# RF_Transceiver_LM6002D.net
KiCad netlist of a schematic drawn in Altium Designer
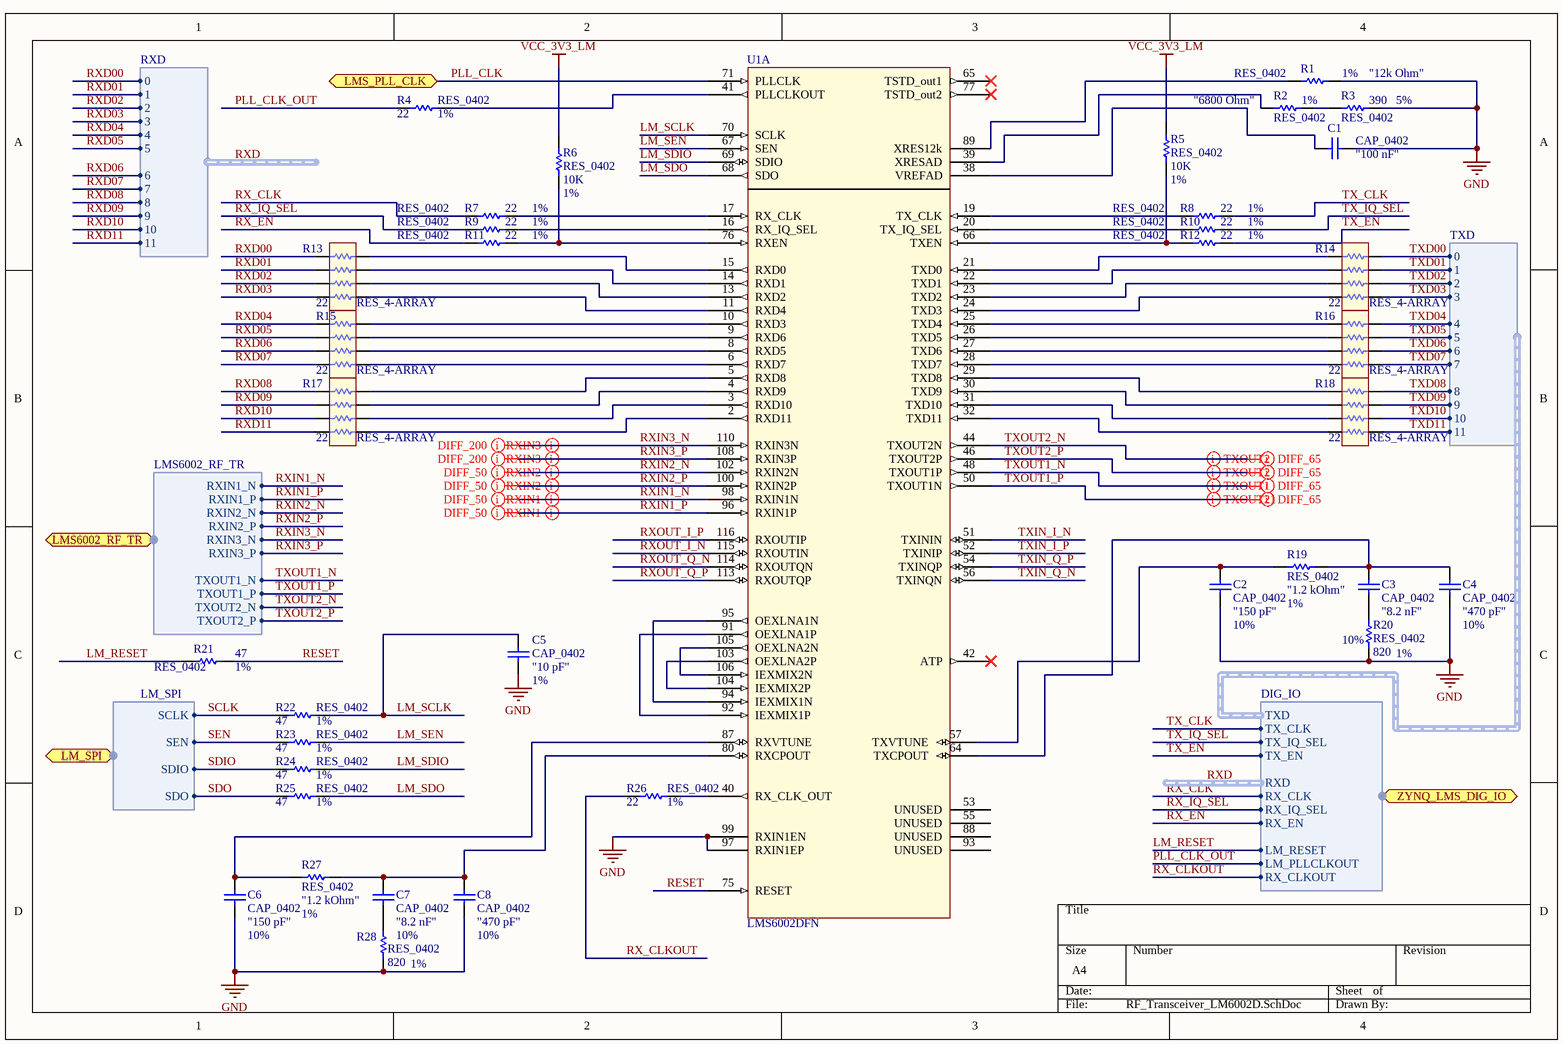
[diagram p0: RF_Transceiver_LM6002D.SchDoc]

(export (version "E")
  (design (tool "Eeschema 10.0.6"))
  (components
    (comp (ref "C1")
      (value "CAP_0402")
      (footprint "CAPC0402(1005)60_N")
      (description "C 100 nF 16 V 0402 X5R")
      (fields
        (field (name "ALTIUM_VALUE") "\"100 nF\"")
        (field (name "PART NUMBER") "\"C0402C104K8PAC\"")
        (field (name "MANUFACTURER") "KEMET")
      )
      (libsource (lib "COMRAD_Database") (part "CAP_0402"))
    )
    (comp (ref "C2")
      (value "CAP_0402")
      (footprint "CAPC0402(1005)60_N")
      (description "C 470pF 50V X7R 10% 0402")
      (fields
        (field (name "ALTIUM_VALUE") "\"150 pF\"")
        (field (name "TOLERANCE") "10%")
        (field (name "PART NUMBER") "\"MCCA000122\"")
        (field (name "MANUFACTURER") "MULTICOMP")
      )
      (libsource (lib "COMRAD_Database") (part "CAP_0402"))
    )
    (comp (ref "C3")
      (value "CAP_0402")
      (footprint "CAPC0402(1005)60_N")
      (description "C 470pF 50V X7R 10% 0402")
      (fields
        (field (name "ALTIUM_VALUE") "\"8.2 nF\"")
        (field (name "TOLERANCE") "10%")
        (field (name "PART NUMBER") "\"MCCA000039\"")
        (field (name "MANUFACTURER") "MULTICOMP")
      )
      (libsource (lib "COMRAD_Database") (part "CAP_0402"))
    )
    (comp (ref "C4")
      (value "CAP_0402")
      (footprint "CAPC0402(1005)60_N")
      (description "C 470pF 50V X7R 10% 0402")
      (fields
        (field (name "ALTIUM_VALUE") "\"470 pF\"")
        (field (name "TOLERANCE") "10%")
        (field (name "PART NUMBER") "\"MCCA000132\"")
        (field (name "MANUFACTURER") "MULTICOMP")
      )
      (libsource (lib "COMRAD_Database") (part "CAP_0402"))
    )
    (comp (ref "C5")
      (value "CAP_0402")
      (footprint "CAPC0402(1005)60_N")
      (description "C 10pF 1% 50V NP0 0402")
      (fields
        (field (name "ALTIUM_VALUE") "\"10 pF\"")
        (field (name "TOLERANCE") "1%")
        (field (name "PART NUMBER") "\"MC0402N100F500CT\"")
        (field (name "MANUFACTURER") "MULTICOMP")
      )
      (libsource (lib "COMRAD_Database") (part "CAP_0402"))
    )
    (comp (ref "C6")
      (value "CAP_0402")
      (footprint "CAPC0402(1005)60_N")
      (description "C 470pF 50V X7R 10% 0402")
      (fields
        (field (name "ALTIUM_VALUE") "\"150 pF\"")
        (field (name "TOLERANCE") "10%")
        (field (name "PART NUMBER") "\"MCCA000122\"")
        (field (name "MANUFACTURER") "MULTICOMP")
      )
      (libsource (lib "COMRAD_Database") (part "CAP_0402"))
    )
    (comp (ref "C7")
      (value "CAP_0402")
      (footprint "CAPC0402(1005)60_N")
      (description "C 470pF 50V X7R 10% 0402")
      (fields
        (field (name "ALTIUM_VALUE") "\"8.2 nF\"")
        (field (name "TOLERANCE") "10%")
        (field (name "PART NUMBER") "\"MCCA000039\"")
        (field (name "MANUFACTURER") "MULTICOMP")
      )
      (libsource (lib "COMRAD_Database") (part "CAP_0402"))
    )
    (comp (ref "C8")
      (value "CAP_0402")
      (footprint "CAPC0402(1005)60_N")
      (description "C 470pF 50V X7R 10% 0402")
      (fields
        (field (name "ALTIUM_VALUE") "\"470 pF\"")
        (field (name "TOLERANCE") "10%")
        (field (name "PART NUMBER") "\"MCCA000132\"")
        (field (name "MANUFACTURER") "MULTICOMP")
      )
      (libsource (lib "COMRAD_Database") (part "CAP_0402"))
    )
    (comp (ref "R1")
      (value "RES_0402")
      (footprint "RESC0402(1005)_N")
      (description "R 12 kOhm 1 % 63 mW 0402")
      (fields
        (field (name "ALTIUM_VALUE") "\"12k Ohm\"")
        (field (name "TOLERANCE") "1%")
        (field (name "PART NUMBER") "\"MC 0.0625W 0402 1% 12K\"")
        (field (name "MANUFACTURER") "MULTICOMP")
      )
      (libsource (lib "COMRAD_Database") (part "RES_0402"))
    )
    (comp (ref "R2")
      (value "RES_0402")
      (footprint "RESC0402(1005)_N")
      (description "R 6800 Ohm 1 % 63 mW 0402")
      (fields
        (field (name "ALTIUM_VALUE") "\"6800 Ohm\"")
        (field (name "TOLERANCE") "1%")
        (field (name "PART NUMBER") "\"232270676802\"")
        (field (name "MANUFACTURER") "PHYCOMP")
      )
      (libsource (lib "COMRAD_Database") (part "RES_0402"))
    )
    (comp (ref "R3")
      (value "RES_0402")
      (footprint "RESC0402(1005)_N")
      (description "390 ohm, 5%, 1/16W, 0402")
      (fields
        (field (name "ALTIUM_VALUE") "390")
        (field (name "TOLERANCE") "5%")
        (field (name "PART NUMBER") "RC0402JR-07390RL")
        (field (name "MANUFACTURER") "Yageo America")
      )
      (libsource (lib "COMRAD_Database") (part "RES_0402"))
    )
    (comp (ref "R4")
      (value "RES_0402")
      (footprint "RESC0402(1005)_N")
      (description "RES 22.0 OHM 1/10W 1% 0402 SMD")
      (fields
        (field (name "ALTIUM_VALUE") "22")
        (field (name "TOLERANCE") "1%")
        (field (name "PART NUMBER") "ERJ-2RKF22R0X")
        (field (name "MANUFACTURER") "Panasonic Electronic Components")
      )
      (libsource (lib "COMRAD_Database") (part "RES_0402"))
    )
    (comp (ref "R5")
      (value "RES_0402")
      (footprint "RESC0402(1005)_N")
      (description "RES 10.0K OHM 1/10W 1% 0402 SMD")
      (fields
        (field (name "ALTIUM_VALUE") "10K")
        (field (name "TOLERANCE") "1%")
        (field (name "PART NUMBER") "ERJ-2RKF1002X")
        (field (name "MANUFACTURER") "Panasonic Electronic Components")
      )
      (libsource (lib "COMRAD_Database") (part "RES_0402"))
    )
    (comp (ref "R6")
      (value "RES_0402")
      (footprint "RESC0402(1005)_N")
      (description "RES 10.0K OHM 1/10W 1% 0402 SMD")
      (fields
        (field (name "ALTIUM_VALUE") "10K")
        (field (name "TOLERANCE") "1%")
        (field (name "PART NUMBER") "ERJ-2RKF1002X")
        (field (name "MANUFACTURER") "Panasonic Electronic Components")
      )
      (libsource (lib "COMRAD_Database") (part "RES_0402"))
    )
    (comp (ref "R7")
      (value "RES_0402")
      (footprint "RESC0402(1005)_N")
      (description "RES 22.0 OHM 1/10W 1% 0402 SMD")
      (fields
        (field (name "ALTIUM_VALUE") "22")
        (field (name "TOLERANCE") "1%")
        (field (name "PART NUMBER") "ERJ-2RKF22R0X")
        (field (name "MANUFACTURER") "Panasonic Electronic Components")
      )
      (libsource (lib "COMRAD_Database") (part "RES_0402"))
    )
    (comp (ref "R8")
      (value "RES_0402")
      (footprint "RESC0402(1005)_N")
      (description "RES 22.0 OHM 1/10W 1% 0402 SMD")
      (fields
        (field (name "ALTIUM_VALUE") "22")
        (field (name "TOLERANCE") "1%")
        (field (name "PART NUMBER") "ERJ-2RKF22R0X")
        (field (name "MANUFACTURER") "Panasonic Electronic Components")
      )
      (libsource (lib "COMRAD_Database") (part "RES_0402"))
    )
    (comp (ref "R9")
      (value "RES_0402")
      (footprint "RESC0402(1005)_N")
      (description "RES 22.0 OHM 1/10W 1% 0402 SMD")
      (fields
        (field (name "ALTIUM_VALUE") "22")
        (field (name "TOLERANCE") "1%")
        (field (name "PART NUMBER") "ERJ-2RKF22R0X")
        (field (name "MANUFACTURER") "Panasonic Electronic Components")
      )
      (libsource (lib "COMRAD_Database") (part "RES_0402"))
    )
    (comp (ref "R10")
      (value "RES_0402")
      (footprint "RESC0402(1005)_N")
      (description "RES 22.0 OHM 1/10W 1% 0402 SMD")
      (fields
        (field (name "ALTIUM_VALUE") "22")
        (field (name "TOLERANCE") "1%")
        (field (name "PART NUMBER") "ERJ-2RKF22R0X")
        (field (name "MANUFACTURER") "Panasonic Electronic Components")
      )
      (libsource (lib "COMRAD_Database") (part "RES_0402"))
    )
    (comp (ref "R11")
      (value "RES_0402")
      (footprint "RESC0402(1005)_N")
      (description "RES 22.0 OHM 1/10W 1% 0402 SMD")
      (fields
        (field (name "ALTIUM_VALUE") "22")
        (field (name "TOLERANCE") "1%")
        (field (name "PART NUMBER") "ERJ-2RKF22R0X")
        (field (name "MANUFACTURER") "Panasonic Electronic Components")
      )
      (libsource (lib "COMRAD_Database") (part "RES_0402"))
    )
    (comp (ref "R12")
      (value "RES_0402")
      (footprint "RESC0402(1005)_N")
      (description "RES 22.0 OHM 1/10W 1% 0402 SMD")
      (fields
        (field (name "ALTIUM_VALUE") "22")
        (field (name "TOLERANCE") "1%")
        (field (name "PART NUMBER") "ERJ-2RKF22R0X")
        (field (name "MANUFACTURER") "Panasonic Electronic Components")
      )
      (libsource (lib "COMRAD_Database") (part "RES_0402"))
    )
    (comp (ref "R13")
      (value "RES_4-ARRAY")
      (footprint "RES_4-ARRAY_YC124-JR-0722RL")
      (description "RES ARRAY 22 OHM 4 RES 0804")
      (fields
        (field (name "ALTIUM_VALUE") "22")
        (field (name "PART NUMBER") "YC124-JR-0722RL")
        (field (name "MANUFACTURER") "Yageo")
      )
      (libsource (lib "COMRAD_Database") (part "RES_4-ARRAY"))
    )
    (comp (ref "R14")
      (value "RES_4-ARRAY")
      (footprint "RES_4-ARRAY_YC124-JR-0722RL")
      (description "RES ARRAY 22 OHM 4 RES 0804")
      (fields
        (field (name "ALTIUM_VALUE") "22")
        (field (name "PART NUMBER") "YC124-JR-0722RL")
        (field (name "MANUFACTURER") "Yageo")
      )
      (libsource (lib "COMRAD_Database") (part "RES_4-ARRAY"))
    )
    (comp (ref "R15")
      (value "RES_4-ARRAY")
      (footprint "RES_4-ARRAY_YC124-JR-0722RL")
      (description "RES ARRAY 22 OHM 4 RES 0804")
      (fields
        (field (name "ALTIUM_VALUE") "22")
        (field (name "PART NUMBER") "YC124-JR-0722RL")
        (field (name "MANUFACTURER") "Yageo")
      )
      (libsource (lib "COMRAD_Database") (part "RES_4-ARRAY"))
    )
    (comp (ref "R16")
      (value "RES_4-ARRAY")
      (footprint "RES_4-ARRAY_YC124-JR-0722RL")
      (description "RES ARRAY 22 OHM 4 RES 0804")
      (fields
        (field (name "ALTIUM_VALUE") "22")
        (field (name "PART NUMBER") "YC124-JR-0722RL")
        (field (name "MANUFACTURER") "Yageo")
      )
      (libsource (lib "COMRAD_Database") (part "RES_4-ARRAY"))
    )
    (comp (ref "R17")
      (value "RES_4-ARRAY")
      (footprint "RES_4-ARRAY_YC124-JR-0722RL")
      (description "RES ARRAY 22 OHM 4 RES 0804")
      (fields
        (field (name "ALTIUM_VALUE") "22")
        (field (name "PART NUMBER") "YC124-JR-0722RL")
        (field (name "MANUFACTURER") "Yageo")
      )
      (libsource (lib "COMRAD_Database") (part "RES_4-ARRAY"))
    )
    (comp (ref "R18")
      (value "RES_4-ARRAY")
      (footprint "RES_4-ARRAY_YC124-JR-0722RL")
      (description "RES ARRAY 22 OHM 4 RES 0804")
      (fields
        (field (name "ALTIUM_VALUE") "22")
        (field (name "PART NUMBER") "YC124-JR-0722RL")
        (field (name "MANUFACTURER") "Yageo")
      )
      (libsource (lib "COMRAD_Database") (part "RES_4-ARRAY"))
    )
    (comp (ref "R19")
      (value "RES_0402")
      (footprint "RESC0402(1005)_N")
      (description "R 1k2 Ohm 1% 63mV 0402")
      (fields
        (field (name "ALTIUM_VALUE") "\"1.2 kOhm\"")
        (field (name "TOLERANCE") "1%")
        (field (name "PART NUMBER") "\"CRCW04021K20FKEAHP\"")
        (field (name "MANUFACTURER") "VISHAY DRALORIC")
      )
      (libsource (lib "COMRAD_Database") (part "RES_0402"))
    )
    (comp (ref "R20")
      (value "RES_0402")
      (footprint "RESC0402(1005)_N")
      (description "RES 820 OHM 1/10W 1% 0402 SMD")
      (fields
        (field (name "ALTIUM_VALUE") "820")
        (field (name "TOLERANCE") "1%")
        (field (name "PART NUMBER") "ERJ-2RKF8200X")
        (field (name "MANUFACTURER") "Panasonic Electronic Components")
      )
      (libsource (lib "COMRAD_Database") (part "RES_0402"))
    )
    (comp (ref "R21")
      (value "RES_0402")
      (footprint "RESC0402(1005)_N")
      (description "RES 47.0 OHM 1/10W 1% 0402 SMD")
      (fields
        (field (name "ALTIUM_VALUE") "47")
        (field (name "TOLERANCE") "1%")
        (field (name "PART NUMBER") "ERJ-2RKF47R0X")
        (field (name "MANUFACTURER") "Panasonic Electronic Components")
      )
      (libsource (lib "COMRAD_Database") (part "RES_0402"))
    )
    (comp (ref "R22")
      (value "RES_0402")
      (footprint "RESC0402(1005)_N")
      (description "RES 47.0 OHM 1/10W 1% 0402 SMD")
      (fields
        (field (name "ALTIUM_VALUE") "47")
        (field (name "TOLERANCE") "1%")
        (field (name "PART NUMBER") "ERJ-2RKF47R0X")
        (field (name "MANUFACTURER") "Panasonic Electronic Components")
      )
      (libsource (lib "COMRAD_Database") (part "RES_0402"))
    )
    (comp (ref "R23")
      (value "RES_0402")
      (footprint "RESC0402(1005)_N")
      (description "RES 47.0 OHM 1/10W 1% 0402 SMD")
      (fields
        (field (name "ALTIUM_VALUE") "47")
        (field (name "TOLERANCE") "1%")
        (field (name "PART NUMBER") "ERJ-2RKF47R0X")
        (field (name "MANUFACTURER") "Panasonic Electronic Components")
      )
      (libsource (lib "COMRAD_Database") (part "RES_0402"))
    )
    (comp (ref "R24")
      (value "RES_0402")
      (footprint "RESC0402(1005)_N")
      (description "RES 47.0 OHM 1/10W 1% 0402 SMD")
      (fields
        (field (name "ALTIUM_VALUE") "47")
        (field (name "TOLERANCE") "1%")
        (field (name "PART NUMBER") "ERJ-2RKF47R0X")
        (field (name "MANUFACTURER") "Panasonic Electronic Components")
      )
      (libsource (lib "COMRAD_Database") (part "RES_0402"))
    )
    (comp (ref "R25")
      (value "RES_0402")
      (footprint "RESC0402(1005)_N")
      (description "RES 47.0 OHM 1/10W 1% 0402 SMD")
      (fields
        (field (name "ALTIUM_VALUE") "47")
        (field (name "TOLERANCE") "1%")
        (field (name "PART NUMBER") "ERJ-2RKF47R0X")
        (field (name "MANUFACTURER") "Panasonic Electronic Components")
      )
      (libsource (lib "COMRAD_Database") (part "RES_0402"))
    )
    (comp (ref "R26")
      (value "RES_0402")
      (footprint "RESC0402(1005)_N")
      (description "RES 22.0 OHM 1/10W 1% 0402 SMD")
      (fields
        (field (name "ALTIUM_VALUE") "22")
        (field (name "TOLERANCE") "1%")
        (field (name "PART NUMBER") "ERJ-2RKF22R0X")
        (field (name "MANUFACTURER") "Panasonic Electronic Components")
      )
      (libsource (lib "COMRAD_Database") (part "RES_0402"))
    )
    (comp (ref "R27")
      (value "RES_0402")
      (footprint "RESC0402(1005)_N")
      (description "R 1k2 Ohm 1% 63mV 0402")
      (fields
        (field (name "ALTIUM_VALUE") "\"1.2 kOhm\"")
        (field (name "TOLERANCE") "1%")
        (field (name "PART NUMBER") "\"CRCW04021K20FKEAHP\"")
        (field (name "MANUFACTURER") "VISHAY DRALORIC")
      )
      (libsource (lib "COMRAD_Database") (part "RES_0402"))
    )
    (comp (ref "R28")
      (value "RES_0402")
      (footprint "RESC0402(1005)_N")
      (description "RES 820 OHM 1/10W 1% 0402 SMD")
      (fields
        (field (name "ALTIUM_VALUE") "820")
        (field (name "TOLERANCE") "1%")
        (field (name "PART NUMBER") "ERJ-2RKF8200X")
        (field (name "MANUFACTURER") "Panasonic Electronic Components")
      )
      (libsource (lib "COMRAD_Database") (part "RES_0402"))
    )
    (comp (ref "U1")
      (value "LMS6002DFN")
      (footprint "RF_Transceiver_LimeMicro_LMS6002D_DQFN-116")
      (description "RF Transceiver LMS6002D, 120 pin DQFN package, 1.8V and 3.3V")
      (fields (field (name "MANUFACTURER") "Lime Micro"))
      (libsource (lib "COMRAD_Database") (part "RF_Transceiver_LimeMicro_LMS6002D"))
    )
  )
  (nets
    (net (code "7") (name "/LM_RESET") (class "Default")
      (node (ref "R21") (pin "1") (pinfunction "1_1") (pintype "passive"))
    )
    (net (code "8") (name "/LM_SCLK") (class "Default")
      (node (ref "C5") (pin "2") (pinfunction "2_2") (pintype "passive"))
      (node (ref "R22") (pin "2") (pinfunction "2_2") (pintype "passive"))
      (node (ref "U1") (pin "70") (pinfunction "SCLK_70") (pintype "input"))
    )
    (net (code "9") (name "/LM_SDIO") (class "Default")
      (node (ref "R24") (pin "2") (pinfunction "2_2") (pintype "passive"))
      (node (ref "U1") (pin "69") (pinfunction "SDIO_69") (pintype "bidirectional"))
    )
    (net (code "10") (name "/LM_SDO") (class "Default")
      (node (ref "R25") (pin "2") (pinfunction "2_2") (pintype "passive"))
      (node (ref "U1") (pin "68") (pinfunction "SDO_68") (pintype "output"))
    )
    (net (code "11") (name "/LM_SEN") (class "Default")
      (node (ref "R23") (pin "2") (pinfunction "2_2") (pintype "passive"))
      (node (ref "U1") (pin "67") (pinfunction "SEN_67") (pintype "input"))
    )
    (net (code "12") (name "/PLL_CLK") (class "Default")
      (node (ref "U1") (pin "71") (pinfunction "PLLCLK_71") (pintype "input"))
    )
    (net (code "13") (name "/PLL_CLK_OUT") (class "Default")
      (node (ref "R4") (pin "1") (pinfunction "1_1") (pintype "passive"))
    )
    (net (code "14") (name "/RESET") (class "Default")
      (node (ref "R21") (pin "2") (pinfunction "2_2") (pintype "passive"))
      (node (ref "U1") (pin "75") (pinfunction "RESET_75") (pintype "input"))
    )
    (net (code "15") (name "/RXD00") (class "Default") (node (ref "R13") (pin "8") (pintype "passive")))
    (net (code "16") (name "/RXD01") (class "Default") (node (ref "R13") (pin "7") (pintype "passive")))
    (net (code "17") (name "/RXD02") (class "Default") (node (ref "R13") (pin "6") (pintype "passive")))
    (net (code "18") (name "/RXD03") (class "Default") (node (ref "R13") (pin "5") (pintype "passive")))
    (net (code "19") (name "/RXD04") (class "Default") (node (ref "R15") (pin "8") (pintype "passive")))
    (net (code "20") (name "/RXD05") (class "Default") (node (ref "R15") (pin "7") (pintype "passive")))
    (net (code "21") (name "/RXD06") (class "Default") (node (ref "R15") (pin "6") (pintype "passive")))
    (net (code "22") (name "/RXD07") (class "Default") (node (ref "R15") (pin "5") (pintype "passive")))
    (net (code "23") (name "/RXD08") (class "Default") (node (ref "R17") (pin "8") (pintype "passive")))
    (net (code "24") (name "/RXD09") (class "Default") (node (ref "R17") (pin "7") (pintype "passive")))
    (net (code "25") (name "/RXD10") (class "Default") (node (ref "R17") (pin "6") (pintype "passive")))
    (net (code "26") (name "/RXD11") (class "Default") (node (ref "R17") (pin "5") (pintype "passive")))
    (net (code "29") (name "/RXIN1_N") (class "Default")
      (node (ref "U1") (pin "98") (pinfunction "RXIN1N_98") (pintype "input"))
    )
    (net (code "30") (name "/RXIN1_P") (class "Default")
      (node (ref "U1") (pin "96") (pinfunction "RXIN1P_96") (pintype "input"))
    )
    (net (code "31") (name "/RXIN2_N") (class "Default")
      (node (ref "U1") (pin "102") (pinfunction "RXIN2N_102") (pintype "input"))
    )
    (net (code "32") (name "/RXIN2_P") (class "Default")
      (node (ref "U1") (pin "100") (pinfunction "RXIN2P_100") (pintype "input"))
    )
    (net (code "33") (name "/RXIN3_N") (class "Default")
      (node (ref "U1") (pin "110") (pinfunction "RXIN3N_110") (pintype "input"))
    )
    (net (code "34") (name "/RXIN3_P") (class "Default")
      (node (ref "U1") (pin "108") (pinfunction "RXIN3P_108") (pintype "input"))
    )
    (net (code "35") (name "/RXOUT_I_N") (class "Default")
      (node (ref "U1") (pin "115") (pinfunction "RXOUTIN_115") (pintype "bidirectional"))
    )
    (net (code "36") (name "/RXOUT_I_P") (class "Default")
      (node (ref "U1") (pin "116") (pinfunction "RXOUTIP_116") (pintype "bidirectional"))
    )
    (net (code "37") (name "/RXOUT_Q_N") (class "Default")
      (node (ref "U1") (pin "114") (pinfunction "RXOUTQN_114") (pintype "bidirectional"))
    )
    (net (code "38") (name "/RXOUT_Q_P") (class "Default")
      (node (ref "U1") (pin "113") (pinfunction "RXOUTQP_113") (pintype "bidirectional"))
    )
    (net (code "39") (name "/RX_CLK") (class "Default")
      (node (ref "R7") (pin "1") (pinfunction "1_1") (pintype "passive"))
    )
    (net (code "40") (name "/RX_CLKOUT") (class "Default")
      (node (ref "R26") (pin "1") (pinfunction "1_1") (pintype "passive"))
    )
    (net (code "41") (name "/RX_EN") (class "Default")
      (node (ref "R11") (pin "1") (pinfunction "1_1") (pintype "passive"))
    )
    (net (code "42") (name "/RX_IQ_SEL") (class "Default")
      (node (ref "R9") (pin "1") (pinfunction "1_1") (pintype "passive"))
    )
    (net (code "43") (name "/SCLK") (class "Default")
      (node (ref "R22") (pin "1") (pinfunction "1_1") (pintype "passive"))
    )
    (net (code "44") (name "/SDIO") (class "Default")
      (node (ref "R24") (pin "1") (pinfunction "1_1") (pintype "passive"))
    )
    (net (code "45") (name "/SDO") (class "Default")
      (node (ref "R25") (pin "1") (pinfunction "1_1") (pintype "passive"))
    )
    (net (code "46") (name "/SEN") (class "Default")
      (node (ref "R23") (pin "1") (pinfunction "1_1") (pintype "passive"))
    )
    (net (code "47") (name "/TXD00") (class "Default") (node (ref "R14") (pin "1") (pintype "passive")))
    (net (code "48") (name "/TXD01") (class "Default") (node (ref "R14") (pin "2") (pintype "passive")))
    (net (code "49") (name "/TXD02") (class "Default") (node (ref "R14") (pin "3") (pintype "passive")))
    (net (code "50") (name "/TXD03") (class "Default") (node (ref "R14") (pin "4") (pintype "passive")))
    (net (code "51") (name "/TXD04") (class "Default") (node (ref "R16") (pin "1") (pintype "passive")))
    (net (code "52") (name "/TXD05") (class "Default") (node (ref "R16") (pin "2") (pintype "passive")))
    (net (code "53") (name "/TXD06") (class "Default") (node (ref "R16") (pin "3") (pintype "passive")))
    (net (code "54") (name "/TXD07") (class "Default") (node (ref "R16") (pin "4") (pintype "passive")))
    (net (code "55") (name "/TXD08") (class "Default") (node (ref "R18") (pin "1") (pintype "passive")))
    (net (code "56") (name "/TXD09") (class "Default") (node (ref "R18") (pin "2") (pintype "passive")))
    (net (code "57") (name "/TXD10") (class "Default") (node (ref "R18") (pin "3") (pintype "passive")))
    (net (code "58") (name "/TXD11") (class "Default") (node (ref "R18") (pin "4") (pintype "passive")))
    (net (code "59") (name "/TXIN_I_N") (class "Default")
      (node (ref "U1") (pin "51") (pinfunction "TXININ_51") (pintype "bidirectional"))
    )
    (net (code "60") (name "/TXIN_I_P") (class "Default")
      (node (ref "U1") (pin "52") (pinfunction "TXINIP_52") (pintype "bidirectional"))
    )
    (net (code "61") (name "/TXIN_Q_N") (class "Default")
      (node (ref "U1") (pin "56") (pinfunction "TXINQN_56") (pintype "bidirectional"))
    )
    (net (code "62") (name "/TXIN_Q_P") (class "Default")
      (node (ref "U1") (pin "54") (pinfunction "TXINQP_54") (pintype "bidirectional"))
    )
    (net (code "63") (name "/TXOUT1_N") (class "Default")
      (node (ref "U1") (pin "48") (pinfunction "TXOUT1P_48") (pintype "output"))
    )
    (net (code "64") (name "/TXOUT1_P") (class "Default")
      (node (ref "U1") (pin "50") (pinfunction "TXOUT1N_50") (pintype "output"))
    )
    (net (code "65") (name "/TXOUT2_N") (class "Default")
      (node (ref "U1") (pin "44") (pinfunction "TXOUT2N_44") (pintype "output"))
    )
    (net (code "66") (name "/TXOUT2_P") (class "Default")
      (node (ref "U1") (pin "46") (pinfunction "TXOUT2P_46") (pintype "output"))
    )
    (net (code "67") (name "/TX_CLK") (class "Default")
      (node (ref "R8") (pin "2") (pinfunction "2_2") (pintype "passive"))
    )
    (net (code "68") (name "/TX_EN") (class "Default")
      (node (ref "R12") (pin "2") (pinfunction "2_2") (pintype "passive"))
    )
    (net (code "69") (name "/TX_IQ_SEL") (class "Default")
      (node (ref "R10") (pin "2") (pinfunction "2_2") (pintype "passive"))
    )
    (net (code "74") (name "GND") (class "Default")
      (node (ref "C1") (pin "2") (pinfunction "2_2") (pintype "passive"))
      (node (ref "C2") (pin "1") (pinfunction "1_1") (pintype "passive"))
      (node (ref "C4") (pin "1") (pinfunction "1_1") (pintype "passive"))
      (node (ref "C5") (pin "1") (pinfunction "1_1") (pintype "passive"))
      (node (ref "C6") (pin "1") (pinfunction "1_1") (pintype "passive"))
      (node (ref "C8") (pin "1") (pinfunction "1_1") (pintype "passive"))
      (node (ref "R1") (pin "2") (pinfunction "2_2") (pintype "passive"))
      (node (ref "R20") (pin "1") (pinfunction "1_1") (pintype "passive"))
      (node (ref "R28") (pin "1") (pinfunction "1_1") (pintype "passive"))
      (node (ref "R3") (pin "2") (pinfunction "2_2") (pintype "passive"))
      (node (ref "U1") (pin "97") (pinfunction "RXIN1EP_97") (pintype "passive"))
      (node (ref "U1") (pin "99") (pinfunction "RXIN1EN_99") (pintype "passive"))
    )
    (net (code "75") (name "Net-(C3-Pad1)") (class "Default")
      (node (ref "C3") (pin "1") (pinfunction "1_1") (pintype "passive"))
      (node (ref "R20") (pin "2") (pinfunction "2_2") (pintype "passive"))
    )
    (net (code "76") (name "Net-(C7-Pad1)") (class "Default")
      (node (ref "C7") (pin "1") (pinfunction "1_1") (pintype "passive"))
      (node (ref "R28") (pin "2") (pinfunction "2_2") (pintype "passive"))
    )
    (net (code "77") (name "Net-(R2-Pad2)") (class "Default")
      (node (ref "R2") (pin "2") (pinfunction "2_2") (pintype "passive"))
      (node (ref "R3") (pin "1") (pinfunction "1_1") (pintype "passive"))
    )
    (net (code "78") (name "Net-(U1A-IEXMIX1N)") (class "Default")
      (node (ref "U1") (pin "94") (pinfunction "IEXMIX1N_94") (pintype "input"))
      (node (ref "U1") (pin "95") (pinfunction "OEXLNA1N_95") (pintype "output"))
    )
    (net (code "79") (name "Net-(U1A-IEXMIX1P)") (class "Default")
      (node (ref "U1") (pin "91") (pinfunction "OEXLNA1P_91") (pintype "output"))
      (node (ref "U1") (pin "92") (pinfunction "IEXMIX1P_92") (pintype "input"))
    )
    (net (code "80") (name "Net-(U1A-IEXMIX2N)") (class "Default")
      (node (ref "U1") (pin "105") (pinfunction "OEXLNA2N_105") (pintype "output"))
      (node (ref "U1") (pin "106") (pinfunction "IEXMIX2N_106") (pintype "input"))
    )
    (net (code "81") (name "Net-(U1A-IEXMIX2P)") (class "Default")
      (node (ref "U1") (pin "103") (pinfunction "OEXLNA2P_103") (pintype "output"))
      (node (ref "U1") (pin "104") (pinfunction "IEXMIX2P_104") (pintype "input"))
    )
    (net (code "82") (name "Net-(U1A-PLLCLKOUT)") (class "Default")
      (node (ref "R4") (pin "2") (pinfunction "2_2") (pintype "passive"))
      (node (ref "U1") (pin "41") (pinfunction "PLLCLKOUT_41") (pintype "output"))
    )
    (net (code "83") (name "Net-(U1A-RXCPOUT)") (class "Default")
      (node (ref "C7") (pin "2") (pinfunction "2_2") (pintype "passive"))
      (node (ref "C8") (pin "2") (pinfunction "2_2") (pintype "passive"))
      (node (ref "R27") (pin "2") (pinfunction "2_2") (pintype "passive"))
      (node (ref "U1") (pin "80") (pinfunction "RXCPOUT_80") (pintype "bidirectional"))
    )
    (net (code "84") (name "Net-(U1A-RXD0)") (class "Default")
      (node (ref "R13") (pin "1") (pintype "passive"))
      (node (ref "U1") (pin "15") (pinfunction "RXD0_15") (pintype "output"))
    )
    (net (code "85") (name "Net-(U1A-RXD1)") (class "Default")
      (node (ref "R13") (pin "2") (pintype "passive"))
      (node (ref "U1") (pin "14") (pinfunction "RXD1_14") (pintype "output"))
    )
    (net (code "86") (name "Net-(U1A-RXD2)") (class "Default")
      (node (ref "R13") (pin "3") (pintype "passive"))
      (node (ref "U1") (pin "13") (pinfunction "RXD2_13") (pintype "output"))
    )
    (net (code "87") (name "Net-(U1A-RXD3)") (class "Default")
      (node (ref "R15") (pin "1") (pintype "passive"))
      (node (ref "U1") (pin "10") (pinfunction "RXD3_10") (pintype "output"))
    )
    (net (code "88") (name "Net-(U1A-RXD4)") (class "Default")
      (node (ref "R13") (pin "4") (pintype "passive"))
      (node (ref "U1") (pin "11") (pinfunction "RXD4_11") (pintype "output"))
    )
    (net (code "89") (name "Net-(U1A-RXD5)") (class "Default")
      (node (ref "R15") (pin "3") (pintype "passive"))
      (node (ref "U1") (pin "8") (pinfunction "RXD5_8") (pintype "output"))
    )
    (net (code "90") (name "Net-(U1A-RXD6)") (class "Default")
      (node (ref "R15") (pin "2") (pintype "passive"))
      (node (ref "U1") (pin "9") (pinfunction "RXD6_9") (pintype "output"))
    )
    (net (code "91") (name "Net-(U1A-RXD7)") (class "Default")
      (node (ref "R15") (pin "4") (pintype "passive"))
      (node (ref "U1") (pin "6") (pinfunction "RXD7_6") (pintype "output"))
    )
    (net (code "92") (name "Net-(U1A-RXD8)") (class "Default")
      (node (ref "R17") (pin "1") (pintype "passive"))
      (node (ref "U1") (pin "5") (pinfunction "RXD8_5") (pintype "output"))
    )
    (net (code "93") (name "Net-(U1A-RXD9)") (class "Default")
      (node (ref "R17") (pin "2") (pintype "passive"))
      (node (ref "U1") (pin "4") (pinfunction "RXD9_4") (pintype "output"))
    )
    (net (code "94") (name "Net-(U1A-RXD10)") (class "Default")
      (node (ref "R17") (pin "3") (pintype "passive"))
      (node (ref "U1") (pin "3") (pinfunction "RXD10_3") (pintype "output"))
    )
    (net (code "95") (name "Net-(U1A-RXD11)") (class "Default")
      (node (ref "R17") (pin "4") (pintype "passive"))
      (node (ref "U1") (pin "2") (pinfunction "RXD11_2") (pintype "output"))
    )
    (net (code "96") (name "Net-(U1A-RXEN)") (class "Default")
      (node (ref "R11") (pin "2") (pinfunction "2_2") (pintype "passive"))
      (node (ref "R6") (pin "1") (pinfunction "1_1") (pintype "passive"))
      (node (ref "U1") (pin "76") (pinfunction "RXEN_76") (pintype "input"))
    )
    (net (code "97") (name "Net-(U1A-RXVTUNE)") (class "Default")
      (node (ref "C6") (pin "2") (pinfunction "2_2") (pintype "passive"))
      (node (ref "R27") (pin "1") (pinfunction "1_1") (pintype "passive"))
      (node (ref "U1") (pin "87") (pinfunction "RXVTUNE_87") (pintype "bidirectional"))
    )
    (net (code "98") (name "Net-(U1A-RX_CLK)") (class "Default")
      (node (ref "R7") (pin "2") (pinfunction "2_2") (pintype "passive"))
      (node (ref "U1") (pin "17") (pinfunction "RX_CLK_17") (pintype "input"))
    )
    (net (code "99") (name "Net-(U1A-RX_CLK_OUT)") (class "Default")
      (node (ref "R26") (pin "2") (pinfunction "2_2") (pintype "passive"))
      (node (ref "U1") (pin "40") (pinfunction "RX_CLK_OUT_40") (pintype "output"))
    )
    (net (code "100") (name "Net-(U1A-RX_IQ_SEL)") (class "Default")
      (node (ref "R9") (pin "2") (pinfunction "2_2") (pintype "passive"))
      (node (ref "U1") (pin "16") (pinfunction "RX_IQ_SEL_16") (pintype "output"))
    )
    (net (code "101") (name "Net-(U1A-TXCPOUT)") (class "Default")
      (node (ref "C3") (pin "2") (pinfunction "2_2") (pintype "passive"))
      (node (ref "C4") (pin "2") (pinfunction "2_2") (pintype "passive"))
      (node (ref "R19") (pin "2") (pinfunction "2_2") (pintype "passive"))
      (node (ref "U1") (pin "64") (pinfunction "TXCPOUT_64") (pintype "bidirectional"))
    )
    (net (code "102") (name "Net-(U1A-TXD0)") (class "Default")
      (node (ref "R14") (pin "8") (pintype "passive"))
      (node (ref "U1") (pin "21") (pinfunction "TXD0_21") (pintype "input"))
    )
    (net (code "103") (name "Net-(U1A-TXD1)") (class "Default")
      (node (ref "R14") (pin "7") (pintype "passive"))
      (node (ref "U1") (pin "22") (pinfunction "TXD1_22") (pintype "input"))
    )
    (net (code "104") (name "Net-(U1A-TXD2)") (class "Default")
      (node (ref "R14") (pin "6") (pintype "passive"))
      (node (ref "U1") (pin "23") (pinfunction "TXD2_23") (pintype "input"))
    )
    (net (code "105") (name "Net-(U1A-TXD3)") (class "Default")
      (node (ref "R14") (pin "5") (pintype "passive"))
      (node (ref "U1") (pin "24") (pinfunction "TXD3_24") (pintype "input"))
    )
    (net (code "106") (name "Net-(U1A-TXD4)") (class "Default")
      (node (ref "R16") (pin "8") (pintype "passive"))
      (node (ref "U1") (pin "25") (pinfunction "TXD4_25") (pintype "input"))
    )
    (net (code "107") (name "Net-(U1A-TXD5)") (class "Default")
      (node (ref "R16") (pin "7") (pintype "passive"))
      (node (ref "U1") (pin "26") (pinfunction "TXD5_26") (pintype "input"))
    )
    (net (code "108") (name "Net-(U1A-TXD6)") (class "Default")
      (node (ref "R16") (pin "6") (pintype "passive"))
      (node (ref "U1") (pin "27") (pinfunction "TXD6_27") (pintype "input"))
    )
    (net (code "109") (name "Net-(U1A-TXD7)") (class "Default")
      (node (ref "R16") (pin "5") (pintype "passive"))
      (node (ref "U1") (pin "28") (pinfunction "TXD7_28") (pintype "input"))
    )
    (net (code "110") (name "Net-(U1A-TXD8)") (class "Default")
      (node (ref "R18") (pin "8") (pintype "passive"))
      (node (ref "U1") (pin "29") (pinfunction "TXD8_29") (pintype "input"))
    )
    (net (code "111") (name "Net-(U1A-TXD9)") (class "Default")
      (node (ref "R18") (pin "7") (pintype "passive"))
      (node (ref "U1") (pin "30") (pinfunction "TXD9_30") (pintype "input"))
    )
    (net (code "112") (name "Net-(U1A-TXD10)") (class "Default")
      (node (ref "R18") (pin "6") (pintype "passive"))
      (node (ref "U1") (pin "31") (pinfunction "TXD10_31") (pintype "input"))
    )
    (net (code "113") (name "Net-(U1A-TXD11)") (class "Default")
      (node (ref "R18") (pin "5") (pintype "passive"))
      (node (ref "U1") (pin "32") (pinfunction "TXD11_32") (pintype "input"))
    )
    (net (code "114") (name "Net-(U1A-TXEN)") (class "Default")
      (node (ref "R12") (pin "1") (pinfunction "1_1") (pintype "passive"))
      (node (ref "R5") (pin "1") (pinfunction "1_1") (pintype "passive"))
      (node (ref "U1") (pin "66") (pinfunction "TXEN_66") (pintype "input"))
    )
    (net (code "115") (name "Net-(U1A-TXVTUNE)") (class "Default")
      (node (ref "C2") (pin "2") (pinfunction "2_2") (pintype "passive"))
      (node (ref "R19") (pin "1") (pinfunction "1_1") (pintype "passive"))
      (node (ref "U1") (pin "57") (pinfunction "TXVTUNE_57") (pintype "bidirectional"))
    )
    (net (code "116") (name "Net-(U1A-TX_CLK)") (class "Default")
      (node (ref "R8") (pin "1") (pinfunction "1_1") (pintype "passive"))
      (node (ref "U1") (pin "19") (pinfunction "TX_CLK_19") (pintype "input"))
    )
    (net (code "117") (name "Net-(U1A-TX_IQ_SEL)") (class "Default")
      (node (ref "R10") (pin "1") (pinfunction "1_1") (pintype "passive"))
      (node (ref "U1") (pin "20") (pinfunction "TX_IQ_SEL_20") (pintype "input"))
    )
    (net (code "118") (name "Net-(U1A-VREFAD)") (class "Default")
      (node (ref "C1") (pin "1") (pinfunction "1_1") (pintype "passive"))
      (node (ref "U1") (pin "38") (pinfunction "VREFAD_38") (pintype "passive"))
    )
    (net (code "119") (name "Net-(U1A-XRES12k)") (class "Default")
      (node (ref "R1") (pin "1") (pinfunction "1_1") (pintype "passive"))
      (node (ref "U1") (pin "89") (pinfunction "XRES12k_89") (pintype "passive"))
    )
    (net (code "120") (name "Net-(U1A-XRESAD)") (class "Default")
      (node (ref "R2") (pin "1") (pinfunction "1_1") (pintype "passive"))
      (node (ref "U1") (pin "39") (pinfunction "XRESAD_39") (pintype "passive"))
    )
    (net (code "121") (name "VCC_3V3_LM") (class "Default")
      (node (ref "R5") (pin "2") (pinfunction "2_2") (pintype "passive"))
      (node (ref "R6") (pin "2") (pinfunction "2_2") (pintype "passive"))
    )
    (net (code "122") (name "unconnected-(U1A-ATP-Pad42)") (class "Default")
      (node (ref "U1") (pin "42") (pinfunction "ATP_42") (pintype "output+no_connect"))
    )
    (net (code "123") (name "unconnected-(U1A-TSTD_out1-Pad65)") (class "Default")
      (node (ref "U1") (pin "65") (pinfunction "TSTD_out1_65") (pintype "output+no_connect"))
    )
    (net (code "124") (name "unconnected-(U1A-TSTD_out2-Pad77)") (class "Default")
      (node (ref "U1") (pin "77") (pinfunction "TSTD_out2_77") (pintype "output+no_connect"))
    )
    (net (code "125") (name "unconnected-(U1A-UNUSED-Pad53)") (class "Default")
      (node (ref "U1") (pin "53") (pinfunction "UNUSED_53") (pintype "power_in"))
    )
    (net (code "126") (name "unconnected-(U1A-UNUSED-Pad55)") (class "Default")
      (node (ref "U1") (pin "55") (pinfunction "UNUSED_55") (pintype "power_in"))
    )
    (net (code "127") (name "unconnected-(U1A-UNUSED-Pad88)") (class "Default")
      (node (ref "U1") (pin "88") (pinfunction "UNUSED_88") (pintype "power_in"))
    )
    (net (code "128") (name "unconnected-(U1A-UNUSED-Pad93)") (class "Default")
      (node (ref "U1") (pin "93") (pinfunction "UNUSED_93") (pintype "power_in"))
    )
  )
)
